# schematic.net
KiCad netlist of a schematic drawn in EAGLE
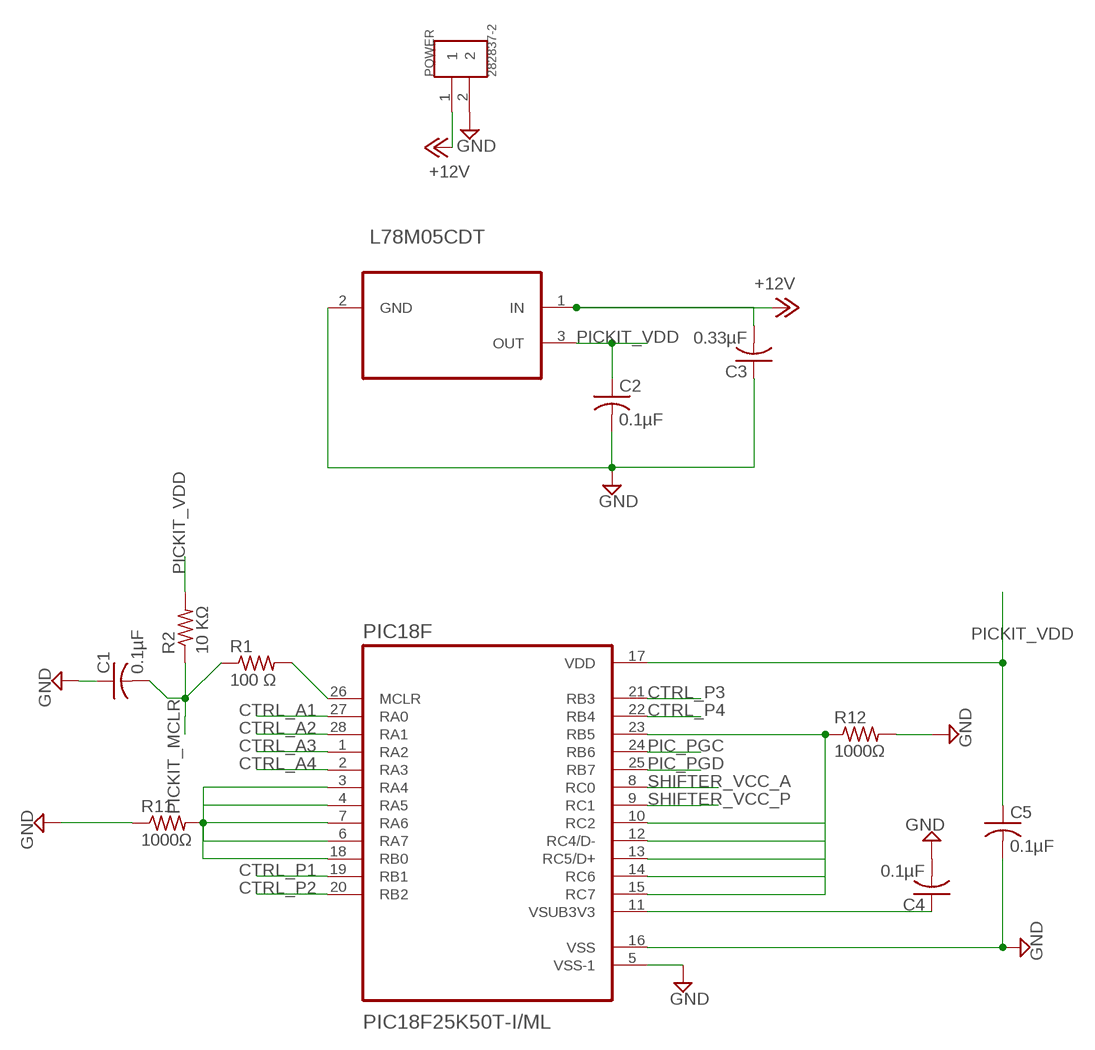
[diagram p0: schematic, sheet 1]
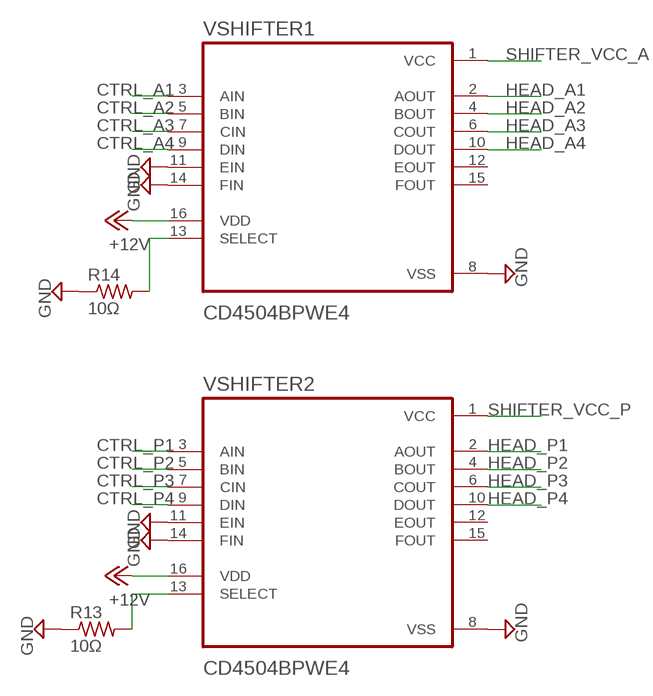
[diagram p1: schematic, sheet 2]
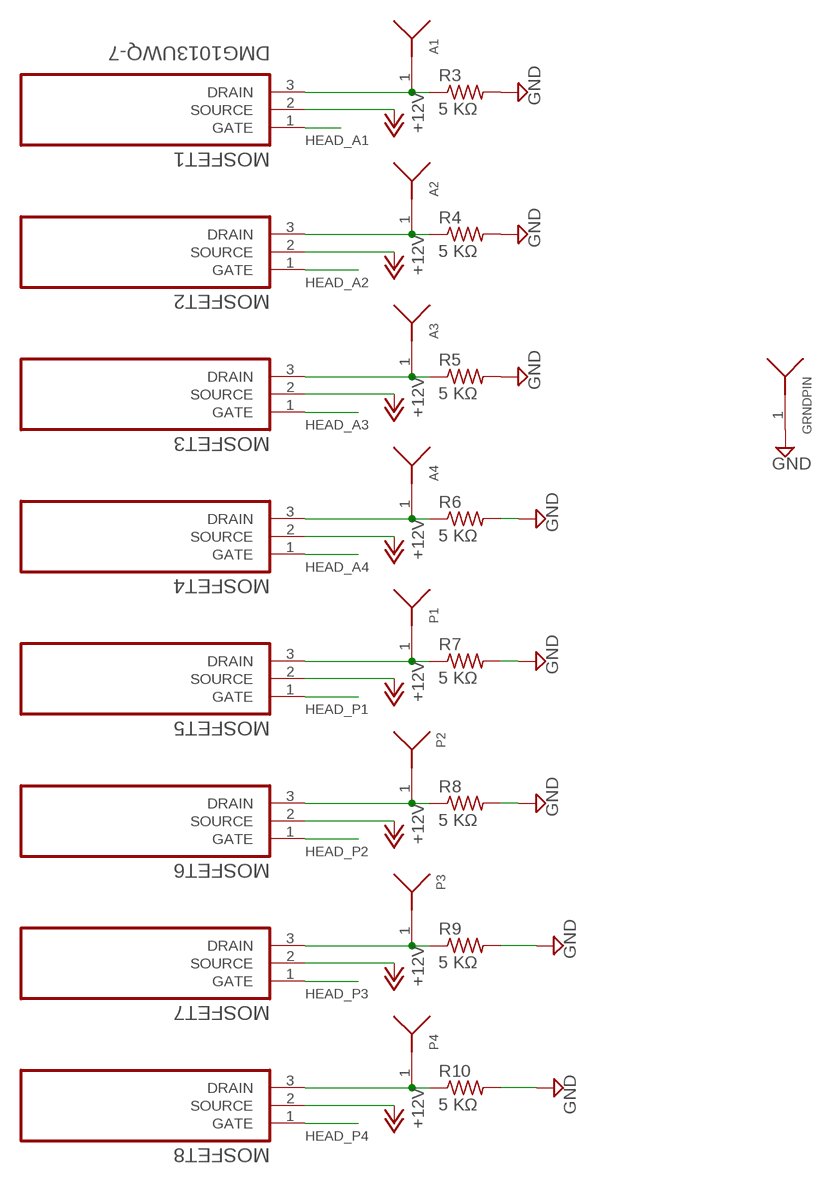
[diagram p2: schematic, sheet 3]
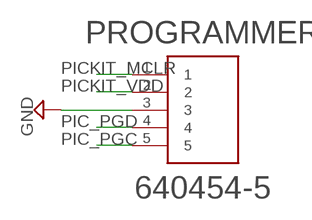
[diagram p3: schematic, sheet 4]

(export (version "E")
  (design (tool "Eeschema 10.0.6"))
  (components
    (comp (ref "PROGRAMMER")
      (value "640454-5")
      (footprint "eagle-import:TE_640454-5")
      (fields (field (name "MF") "TE Connectivity"))
      (libsource (lib "eagle-import") (part "640454-5"))
    )
    (comp (ref "C1")
      (value "0.1µF")
      (footprint "eagle-import:C0603")
      (fields (field (name "MPN") "B32529C0104J000"))
      (libsource (lib "eagle-import") (part "C-USC0603"))
    )
    (comp (ref "C2")
      (value "0.1µF")
      (footprint "eagle-import:C0603")
      (fields (field (name "MPN") "B32529C0104J000"))
      (libsource (lib "eagle-import") (part "C-USC0603"))
    )
    (comp (ref "C3")
      (value "0.33µF")
      (footprint "eagle-import:C0603")
      (libsource (lib "eagle-import") (part "C-USC0603"))
    )
    (comp (ref "C4")
      (value "0.1µF")
      (footprint "eagle-import:C0603")
      (fields (field (name "MPN") "B32529C0104J000"))
      (libsource (lib "eagle-import") (part "C-USC0603"))
    )
    (comp (ref "C5")
      (value "0.1µF")
      (footprint "eagle-import:C0603")
      (fields (field (name "MPN") "B32529C0104J000"))
      (libsource (lib "eagle-import") (part "C-USC0603"))
    )
    (comp (ref "L78M05CDT")
      (value "L78M05CDT")
      (footprint "eagle-import:TO225P972X240-3N")
      (fields (field (name "MF") "STMicroelectronics") (field (name "MP") "L78M05CDT-TR"))
      (libsource (lib "eagle-import") (part "L78M05CDT"))
    )
    (comp (ref "PIC18F")
      (value "PIC18F25K50T-I/ML")
      (footprint "eagle-import:QFN65P600X600X100-29N")
      (fields (field (name "MF") "Microchip"))
      (libsource (lib "eagle-import") (part "PIC18F25K50T-I/ML"))
    )
    (comp (ref "POWER")
      (value "282837-2")
      (footprint "eagle-import:TE_282837-2")
      (fields (field (name "MF") "TE Connectivity"))
      (libsource (lib "eagle-import") (part "282837-2"))
    )
    (comp (ref "R1")
      (value "100 Ω")
      (footprint "eagle-import:R0805")
      (libsource (lib "eagle-import") (part "resistor_348_R-US_R0805"))
    )
    (comp (ref "R2")
      (value "10 KΩ")
      (footprint "eagle-import:R0805")
      (libsource (lib "eagle-import") (part "resistor_348_R-US_R0805"))
    )
    (comp (ref "R11")
      (value "1000Ω")
      (footprint "eagle-import:R0603")
      (libsource (lib "eagle-import") (part "resistor_348_R-US_R0603"))
    )
    (comp (ref "R12")
      (value "1000Ω")
      (footprint "eagle-import:R0603")
      (libsource (lib "eagle-import") (part "resistor_348_R-US_R0603"))
    )
    (comp (ref "A1")
      (value "0930")
      (footprint "eagle-import:0930")
      (fields (field (name "MF") "Mill-Max Manufacturing") (field (name "MP") "0926-1-15-20-75-14-11-0"))
      (libsource (lib "eagle-import") (part "0930"))
    )
    (comp (ref "A2")
      (value "0930")
      (footprint "eagle-import:0930")
      (fields (field (name "MF") "Mill-Max Manufacturing") (field (name "MP") "0926-1-15-20-75-14-11-0"))
      (libsource (lib "eagle-import") (part "0930"))
    )
    (comp (ref "A3")
      (value "0930")
      (footprint "eagle-import:0930")
      (fields (field (name "MF") "Mill-Max Manufacturing") (field (name "MP") "0926-1-15-20-75-14-11-0"))
      (libsource (lib "eagle-import") (part "0930"))
    )
    (comp (ref "A4")
      (value "0930")
      (footprint "eagle-import:0930")
      (fields (field (name "MF") "Mill-Max Manufacturing") (field (name "MP") "0926-1-15-20-75-14-11-0"))
      (libsource (lib "eagle-import") (part "0930"))
    )
    (comp (ref "GRNDPIN")
      (value "0930")
      (footprint "eagle-import:0930")
      (fields (field (name "MF") "Mill-Max Manufacturing") (field (name "MP") "0926-1-15-20-75-14-11-0"))
      (libsource (lib "eagle-import") (part "0930"))
    )
    (comp (ref "MOSFET1")
      (value "DMG1013UWQ-7")
      (footprint "eagle-import:SOT65P210X110-3N")
      (fields (field (name "MF") "Diodes Inc."))
      (libsource (lib "eagle-import") (part "DMG1013UWQ-7"))
    )
    (comp (ref "MOSFET2")
      (value "DMG1013UWQ-7")
      (footprint "eagle-import:SOT65P210X110-3N")
      (fields (field (name "MF") "Diodes Inc."))
      (libsource (lib "eagle-import") (part "DMG1013UWQ-7"))
    )
    (comp (ref "MOSFET3")
      (value "DMG1013UWQ-7")
      (footprint "eagle-import:SOT65P210X110-3N")
      (fields (field (name "MF") "Diodes Inc."))
      (libsource (lib "eagle-import") (part "DMG1013UWQ-7"))
    )
    (comp (ref "MOSFET4")
      (value "DMG1013UWQ-7")
      (footprint "eagle-import:SOT65P210X110-3N")
      (fields (field (name "MF") "Diodes Inc."))
      (libsource (lib "eagle-import") (part "DMG1013UWQ-7"))
    )
    (comp (ref "MOSFET5")
      (value "DMG1013UWQ-7")
      (footprint "eagle-import:SOT65P210X110-3N")
      (fields (field (name "MF") "Diodes Inc."))
      (libsource (lib "eagle-import") (part "DMG1013UWQ-7"))
    )
    (comp (ref "MOSFET6")
      (value "DMG1013UWQ-7")
      (footprint "eagle-import:SOT65P210X110-3N")
      (fields (field (name "MF") "Diodes Inc."))
      (libsource (lib "eagle-import") (part "DMG1013UWQ-7"))
    )
    (comp (ref "MOSFET7")
      (value "DMG1013UWQ-7")
      (footprint "eagle-import:SOT65P210X110-3N")
      (fields (field (name "MF") "Diodes Inc."))
      (libsource (lib "eagle-import") (part "DMG1013UWQ-7"))
    )
    (comp (ref "MOSFET8")
      (value "DMG1013UWQ-7")
      (footprint "eagle-import:SOT65P210X110-3N")
      (fields (field (name "MF") "Diodes Inc."))
      (libsource (lib "eagle-import") (part "DMG1013UWQ-7"))
    )
    (comp (ref "P1")
      (value "0930")
      (footprint "eagle-import:0930")
      (fields (field (name "MF") "Mill-Max Manufacturing") (field (name "MP") "0926-1-15-20-75-14-11-0"))
      (libsource (lib "eagle-import") (part "0930"))
    )
    (comp (ref "P2")
      (value "0930")
      (footprint "eagle-import:0930")
      (fields (field (name "MF") "Mill-Max Manufacturing") (field (name "MP") "0926-1-15-20-75-14-11-0"))
      (libsource (lib "eagle-import") (part "0930"))
    )
    (comp (ref "P3")
      (value "0930")
      (footprint "eagle-import:0930")
      (fields (field (name "MF") "Mill-Max Manufacturing") (field (name "MP") "0926-1-15-20-75-14-11-0"))
      (libsource (lib "eagle-import") (part "0930"))
    )
    (comp (ref "P4")
      (value "0930")
      (footprint "eagle-import:0930")
      (fields (field (name "MF") "Mill-Max Manufacturing") (field (name "MP") "0926-1-15-20-75-14-11-0"))
      (libsource (lib "eagle-import") (part "0930"))
    )
    (comp (ref "R3")
      (value "5 KΩ")
      (footprint "eagle-import:R0603")
      (libsource (lib "eagle-import") (part "resistor_348_R-US_R0603"))
    )
    (comp (ref "R4")
      (value "5 KΩ")
      (footprint "eagle-import:R0603")
      (libsource (lib "eagle-import") (part "resistor_348_R-US_R0603"))
    )
    (comp (ref "R5")
      (value "5 KΩ")
      (footprint "eagle-import:R0603")
      (libsource (lib "eagle-import") (part "resistor_348_R-US_R0603"))
    )
    (comp (ref "R6")
      (value "5 KΩ")
      (footprint "eagle-import:R0603")
      (libsource (lib "eagle-import") (part "resistor_348_R-US_R0603"))
    )
    (comp (ref "R7")
      (value "5 KΩ")
      (footprint "eagle-import:R0603")
      (libsource (lib "eagle-import") (part "resistor_348_R-US_R0603"))
    )
    (comp (ref "R8")
      (value "5 KΩ")
      (footprint "eagle-import:R0603")
      (libsource (lib "eagle-import") (part "resistor_348_R-US_R0603"))
    )
    (comp (ref "R9")
      (value "5 KΩ")
      (footprint "eagle-import:R0603")
      (libsource (lib "eagle-import") (part "resistor_348_R-US_R0603"))
    )
    (comp (ref "R10")
      (value "5 KΩ")
      (footprint "eagle-import:R0603")
      (libsource (lib "eagle-import") (part "resistor_348_R-US_R0603"))
    )
    (comp (ref "R13")
      (value "10Ω")
      (footprint "eagle-import:R0603")
      (libsource (lib "eagle-import") (part "R-US_R0603"))
    )
    (comp (ref "R14")
      (value "10Ω")
      (footprint "eagle-import:R0603")
      (libsource (lib "eagle-import") (part "R-US_R0603"))
    )
    (comp (ref "VSHIFTER1")
      (value "CD4504BPWE4")
      (footprint "eagle-import:SOP65P640X120-16N")
      (fields (field (name "MF") "Texas Instruments"))
      (libsource (lib "eagle-import") (part "CD4504BPWE4"))
    )
    (comp (ref "VSHIFTER2")
      (value "CD4504BPWE4")
      (footprint "eagle-import:SOP65P640X120-16N")
      (fields (field (name "MF") "Texas Instruments"))
      (libsource (lib "eagle-import") (part "CD4504BPWE4"))
    )
  )
  (nets
    (net (code "1") (name "+12V") (class "Default")
      (node (ref "C3") (pin "2") (pinfunction "2_2") (pintype "passive"))
      (node (ref "L78M05CDT") (pin "1") (pinfunction "IN_1") (pintype "input"))
      (node (ref "MOSFET1") (pin "2") (pinfunction "SOURCE_2") (pintype "bidirectional"))
      (node (ref "MOSFET2") (pin "2") (pinfunction "SOURCE_2") (pintype "bidirectional"))
      (node (ref "MOSFET3") (pin "2") (pinfunction "SOURCE_2") (pintype "bidirectional"))
      (node (ref "MOSFET4") (pin "2") (pinfunction "SOURCE_2") (pintype "bidirectional"))
      (node (ref "MOSFET5") (pin "2") (pinfunction "SOURCE_2") (pintype "bidirectional"))
      (node (ref "MOSFET6") (pin "2") (pinfunction "SOURCE_2") (pintype "bidirectional"))
      (node (ref "MOSFET7") (pin "2") (pinfunction "SOURCE_2") (pintype "bidirectional"))
      (node (ref "MOSFET8") (pin "2") (pinfunction "SOURCE_2") (pintype "bidirectional"))
      (node (ref "POWER") (pin "1") (pinfunction "1_1") (pintype "passive"))
      (node (ref "VSHIFTER1") (pin "16") (pinfunction "VDD_16") (pintype "bidirectional"))
      (node (ref "VSHIFTER2") (pin "16") (pinfunction "VDD_16") (pintype "bidirectional"))
    )
    (net (code "2") (name "CTRL_A1") (class "Default")
      (node (ref "PIC18F") (pin "27") (pinfunction "RA0_27") (pintype "bidirectional"))
      (node (ref "VSHIFTER1") (pin "3") (pinfunction "AIN_3") (pintype "input"))
    )
    (net (code "3") (name "CTRL_A2") (class "Default")
      (node (ref "PIC18F") (pin "28") (pinfunction "RA1_28") (pintype "bidirectional"))
      (node (ref "VSHIFTER1") (pin "5") (pinfunction "BIN_5") (pintype "input"))
    )
    (net (code "4") (name "CTRL_A3") (class "Default")
      (node (ref "PIC18F") (pin "1") (pinfunction "RA2_1") (pintype "bidirectional"))
      (node (ref "VSHIFTER1") (pin "7") (pinfunction "CIN_7") (pintype "input"))
    )
    (net (code "5") (name "CTRL_A4") (class "Default")
      (node (ref "PIC18F") (pin "2") (pinfunction "RA3_2") (pintype "bidirectional"))
      (node (ref "VSHIFTER1") (pin "9") (pinfunction "DIN_9") (pintype "input"))
    )
    (net (code "6") (name "CTRL_P1") (class "Default")
      (node (ref "PIC18F") (pin "19") (pinfunction "RB1_19") (pintype "bidirectional"))
      (node (ref "VSHIFTER2") (pin "3") (pinfunction "AIN_3") (pintype "input"))
    )
    (net (code "7") (name "CTRL_P2") (class "Default")
      (node (ref "PIC18F") (pin "20") (pinfunction "RB2_20") (pintype "bidirectional"))
      (node (ref "VSHIFTER2") (pin "5") (pinfunction "BIN_5") (pintype "input"))
    )
    (net (code "8") (name "CTRL_P3") (class "Default")
      (node (ref "PIC18F") (pin "21") (pinfunction "RB3_21") (pintype "bidirectional"))
      (node (ref "VSHIFTER2") (pin "7") (pinfunction "CIN_7") (pintype "input"))
    )
    (net (code "9") (name "CTRL_P4") (class "Default")
      (node (ref "PIC18F") (pin "22") (pinfunction "RB4_22") (pintype "bidirectional"))
      (node (ref "VSHIFTER2") (pin "9") (pinfunction "DIN_9") (pintype "input"))
    )
    (net (code "10") (name "GND") (class "Default")
      (node (ref "C1") (pin "1") (pinfunction "1_1") (pintype "passive"))
      (node (ref "C2") (pin "2") (pinfunction "2_2") (pintype "passive"))
      (node (ref "C3") (pin "1") (pinfunction "1_1") (pintype "passive"))
      (node (ref "C4") (pin "2") (pinfunction "2_2") (pintype "passive"))
      (node (ref "C5") (pin "2") (pinfunction "2_2") (pintype "passive"))
      (node (ref "GRNDPIN") (pin "1") (pinfunction "1_1") (pintype "passive"))
      (node (ref "L78M05CDT") (pin "2") (pinfunction "GND_2") (pintype "output"))
      (node (ref "PIC18F") (pin "16") (pinfunction "VSS_16") (pintype "power_in"))
      (node (ref "PIC18F") (pin "5") (pinfunction "VSS-1_5") (pintype "power_in"))
      (node (ref "POWER") (pin "2") (pinfunction "2_2") (pintype "passive"))
      (node (ref "PROGRAMMER") (pin "3") (pinfunction "3_3") (pintype "passive"))
      (node (ref "R10") (pin "2") (pinfunction "2_2") (pintype "passive"))
      (node (ref "R11") (pin "1") (pinfunction "1_1") (pintype "passive"))
      (node (ref "R12") (pin "2") (pinfunction "2_2") (pintype "passive"))
      (node (ref "R13") (pin "1") (pinfunction "1_1") (pintype "passive"))
      (node (ref "R14") (pin "1") (pinfunction "1_1") (pintype "passive"))
      (node (ref "R3") (pin "2") (pinfunction "2_2") (pintype "passive"))
      (node (ref "R4") (pin "2") (pinfunction "2_2") (pintype "passive"))
      (node (ref "R5") (pin "2") (pinfunction "2_2") (pintype "passive"))
      (node (ref "R6") (pin "2") (pinfunction "2_2") (pintype "passive"))
      (node (ref "R7") (pin "2") (pinfunction "2_2") (pintype "passive"))
      (node (ref "R8") (pin "2") (pinfunction "2_2") (pintype "passive"))
      (node (ref "R9") (pin "2") (pinfunction "2_2") (pintype "passive"))
      (node (ref "VSHIFTER1") (pin "11") (pinfunction "EIN_11") (pintype "input"))
      (node (ref "VSHIFTER1") (pin "14") (pinfunction "FIN_14") (pintype "input"))
      (node (ref "VSHIFTER1") (pin "8") (pinfunction "VSS_8") (pintype "power_in"))
      (node (ref "VSHIFTER2") (pin "11") (pinfunction "EIN_11") (pintype "input"))
      (node (ref "VSHIFTER2") (pin "14") (pinfunction "FIN_14") (pintype "input"))
      (node (ref "VSHIFTER2") (pin "8") (pinfunction "VSS_8") (pintype "power_in"))
    )
    (net (code "11") (name "HEAD_A1") (class "Default")
      (node (ref "MOSFET1") (pin "1") (pinfunction "GATE_1") (pintype "bidirectional"))
      (node (ref "VSHIFTER1") (pin "2") (pinfunction "AOUT_2") (pintype "output"))
    )
    (net (code "12") (name "HEAD_A2") (class "Default")
      (node (ref "MOSFET2") (pin "1") (pinfunction "GATE_1") (pintype "bidirectional"))
      (node (ref "VSHIFTER1") (pin "4") (pinfunction "BOUT_4") (pintype "output"))
    )
    (net (code "13") (name "HEAD_A3") (class "Default")
      (node (ref "MOSFET3") (pin "1") (pinfunction "GATE_1") (pintype "bidirectional"))
      (node (ref "VSHIFTER1") (pin "6") (pinfunction "COUT_6") (pintype "output"))
    )
    (net (code "14") (name "HEAD_A4") (class "Default")
      (node (ref "MOSFET4") (pin "1") (pinfunction "GATE_1") (pintype "bidirectional"))
      (node (ref "VSHIFTER1") (pin "10") (pinfunction "DOUT_10") (pintype "output"))
    )
    (net (code "15") (name "HEAD_P1") (class "Default")
      (node (ref "MOSFET5") (pin "1") (pinfunction "GATE_1") (pintype "bidirectional"))
      (node (ref "VSHIFTER2") (pin "2") (pinfunction "AOUT_2") (pintype "output"))
    )
    (net (code "16") (name "HEAD_P2") (class "Default")
      (node (ref "MOSFET6") (pin "1") (pinfunction "GATE_1") (pintype "bidirectional"))
      (node (ref "VSHIFTER2") (pin "4") (pinfunction "BOUT_4") (pintype "output"))
    )
    (net (code "17") (name "HEAD_P3") (class "Default")
      (node (ref "MOSFET7") (pin "1") (pinfunction "GATE_1") (pintype "bidirectional"))
      (node (ref "VSHIFTER2") (pin "6") (pinfunction "COUT_6") (pintype "output"))
    )
    (net (code "18") (name "HEAD_P4") (class "Default")
      (node (ref "MOSFET8") (pin "1") (pinfunction "GATE_1") (pintype "bidirectional"))
      (node (ref "VSHIFTER2") (pin "10") (pinfunction "DOUT_10") (pintype "output"))
    )
    (net (code "19") (name "Net-(MOSFET1-DRAIN)") (class "Default")
      (node (ref "A1") (pin "1") (pinfunction "1_1") (pintype "passive"))
      (node (ref "MOSFET1") (pin "3") (pinfunction "DRAIN_3") (pintype "bidirectional"))
      (node (ref "R3") (pin "1") (pinfunction "1_1") (pintype "passive"))
    )
    (net (code "20") (name "Net-(MOSFET2-DRAIN)") (class "Default")
      (node (ref "A2") (pin "1") (pinfunction "1_1") (pintype "passive"))
      (node (ref "MOSFET2") (pin "3") (pinfunction "DRAIN_3") (pintype "bidirectional"))
      (node (ref "R4") (pin "1") (pinfunction "1_1") (pintype "passive"))
    )
    (net (code "21") (name "Net-(MOSFET3-DRAIN)") (class "Default")
      (node (ref "A3") (pin "1") (pinfunction "1_1") (pintype "passive"))
      (node (ref "MOSFET3") (pin "3") (pinfunction "DRAIN_3") (pintype "bidirectional"))
      (node (ref "R5") (pin "1") (pinfunction "1_1") (pintype "passive"))
    )
    (net (code "22") (name "Net-(MOSFET4-DRAIN)") (class "Default")
      (node (ref "A4") (pin "1") (pinfunction "1_1") (pintype "passive"))
      (node (ref "MOSFET4") (pin "3") (pinfunction "DRAIN_3") (pintype "bidirectional"))
      (node (ref "R6") (pin "1") (pinfunction "1_1") (pintype "passive"))
    )
    (net (code "23") (name "Net-(MOSFET5-DRAIN)") (class "Default")
      (node (ref "MOSFET5") (pin "3") (pinfunction "DRAIN_3") (pintype "bidirectional"))
      (node (ref "P1") (pin "1") (pinfunction "1_1") (pintype "passive"))
      (node (ref "R7") (pin "1") (pinfunction "1_1") (pintype "passive"))
    )
    (net (code "24") (name "Net-(MOSFET6-DRAIN)") (class "Default")
      (node (ref "MOSFET6") (pin "3") (pinfunction "DRAIN_3") (pintype "bidirectional"))
      (node (ref "P2") (pin "1") (pinfunction "1_1") (pintype "passive"))
      (node (ref "R8") (pin "1") (pinfunction "1_1") (pintype "passive"))
    )
    (net (code "25") (name "Net-(MOSFET7-DRAIN)") (class "Default")
      (node (ref "MOSFET7") (pin "3") (pinfunction "DRAIN_3") (pintype "bidirectional"))
      (node (ref "P3") (pin "1") (pinfunction "1_1") (pintype "passive"))
      (node (ref "R9") (pin "1") (pinfunction "1_1") (pintype "passive"))
    )
    (net (code "26") (name "Net-(MOSFET8-DRAIN)") (class "Default")
      (node (ref "MOSFET8") (pin "3") (pinfunction "DRAIN_3") (pintype "bidirectional"))
      (node (ref "P4") (pin "1") (pinfunction "1_1") (pintype "passive"))
      (node (ref "R10") (pin "1") (pinfunction "1_1") (pintype "passive"))
    )
    (net (code "27") (name "Net-(PIC18F-MCLR)") (class "Default")
      (node (ref "PIC18F") (pin "26") (pinfunction "MCLR_26") (pintype "bidirectional"))
      (node (ref "R1") (pin "2") (pinfunction "2_2") (pintype "passive"))
    )
    (net (code "28") (name "Net-(PIC18F-RA4)") (class "Default")
      (node (ref "PIC18F") (pin "18") (pinfunction "RB0_18") (pintype "bidirectional"))
      (node (ref "PIC18F") (pin "3") (pinfunction "RA4_3") (pintype "bidirectional"))
      (node (ref "PIC18F") (pin "4") (pinfunction "RA5_4") (pintype "bidirectional"))
      (node (ref "PIC18F") (pin "6") (pinfunction "RA7_6") (pintype "bidirectional"))
      (node (ref "PIC18F") (pin "7") (pinfunction "RA6_7") (pintype "bidirectional"))
      (node (ref "R11") (pin "2") (pinfunction "2_2") (pintype "passive"))
    )
    (net (code "29") (name "Net-(PIC18F-RB5)") (class "Default")
      (node (ref "PIC18F") (pin "10") (pinfunction "RC2_10") (pintype "bidirectional"))
      (node (ref "PIC18F") (pin "12") (pinfunction "RC4/D-_12") (pintype "bidirectional"))
      (node (ref "PIC18F") (pin "13") (pinfunction "RC5/D+_13") (pintype "bidirectional"))
      (node (ref "PIC18F") (pin "14") (pinfunction "RC6_14") (pintype "bidirectional"))
      (node (ref "PIC18F") (pin "15") (pinfunction "RC7_15") (pintype "bidirectional"))
      (node (ref "PIC18F") (pin "23") (pinfunction "RB5_23") (pintype "bidirectional"))
      (node (ref "R12") (pin "1") (pinfunction "1_1") (pintype "passive"))
    )
    (net (code "30") (name "Net-(PIC18F-VSUB3V3)") (class "Default")
      (node (ref "C4") (pin "1") (pinfunction "1_1") (pintype "passive"))
      (node (ref "PIC18F") (pin "11") (pinfunction "VSUB3V3_11") (pintype "bidirectional"))
    )
    (net (code "31") (name "Net-(VSHIFTER1-SELECT)") (class "Default")
      (node (ref "R14") (pin "2") (pinfunction "2_2") (pintype "passive"))
      (node (ref "VSHIFTER1") (pin "13") (pinfunction "SELECT_13") (pintype "bidirectional"))
    )
    (net (code "32") (name "Net-(VSHIFTER2-SELECT)") (class "Default")
      (node (ref "R13") (pin "2") (pinfunction "2_2") (pintype "passive"))
      (node (ref "VSHIFTER2") (pin "13") (pinfunction "SELECT_13") (pintype "bidirectional"))
    )
    (net (code "33") (name "PICKIT_MCLR") (class "Default")
      (node (ref "C1") (pin "2") (pinfunction "2_2") (pintype "passive"))
      (node (ref "PROGRAMMER") (pin "1") (pinfunction "1_1") (pintype "passive"))
      (node (ref "R1") (pin "1") (pinfunction "1_1") (pintype "passive"))
      (node (ref "R2") (pin "1") (pinfunction "1_1") (pintype "passive"))
    )
    (net (code "34") (name "PICKIT_VDD") (class "Default")
      (node (ref "C2") (pin "1") (pinfunction "1_1") (pintype "passive"))
      (node (ref "C5") (pin "1") (pinfunction "1_1") (pintype "passive"))
      (node (ref "L78M05CDT") (pin "3") (pinfunction "OUT_3") (pintype "passive"))
      (node (ref "PIC18F") (pin "17") (pinfunction "VDD_17") (pintype "power_in"))
      (node (ref "PROGRAMMER") (pin "2") (pinfunction "2_2") (pintype "passive"))
      (node (ref "R2") (pin "2") (pinfunction "2_2") (pintype "passive"))
    )
    (net (code "35") (name "PIC_PGC") (class "Default")
      (node (ref "PIC18F") (pin "24") (pinfunction "RB6_24") (pintype "bidirectional"))
      (node (ref "PROGRAMMER") (pin "5") (pinfunction "5_5") (pintype "passive"))
    )
    (net (code "36") (name "PIC_PGD") (class "Default")
      (node (ref "PIC18F") (pin "25") (pinfunction "RB7_25") (pintype "bidirectional"))
      (node (ref "PROGRAMMER") (pin "4") (pinfunction "4_4") (pintype "passive"))
    )
    (net (code "37") (name "SHIFTER_VCC_A") (class "Default")
      (node (ref "PIC18F") (pin "8") (pinfunction "RC0_8") (pintype "bidirectional"))
      (node (ref "VSHIFTER1") (pin "1") (pinfunction "VCC_1") (pintype "power_in"))
    )
    (net (code "38") (name "SHIFTER_VCC_P") (class "Default")
      (node (ref "PIC18F") (pin "9") (pinfunction "RC1_9") (pintype "bidirectional"))
      (node (ref "VSHIFTER2") (pin "1") (pinfunction "VCC_1") (pintype "power_in"))
    )
    (net (code "39") (name "unconnected-(VSHIFTER1-EOUT-Pad12)") (class "Default")
      (node (ref "VSHIFTER1") (pin "12") (pinfunction "EOUT_12") (pintype "output"))
    )
    (net (code "40") (name "unconnected-(VSHIFTER1-FOUT-Pad15)") (class "Default")
      (node (ref "VSHIFTER1") (pin "15") (pinfunction "FOUT_15") (pintype "output"))
    )
    (net (code "41") (name "unconnected-(VSHIFTER2-EOUT-Pad12)") (class "Default")
      (node (ref "VSHIFTER2") (pin "12") (pinfunction "EOUT_12") (pintype "output"))
    )
    (net (code "42") (name "unconnected-(VSHIFTER2-FOUT-Pad15)") (class "Default")
      (node (ref "VSHIFTER2") (pin "15") (pinfunction "FOUT_15") (pintype "output"))
    )
  )
)
